# Top_Level.net
KiCad netlist of a schematic drawn in Altium Designer
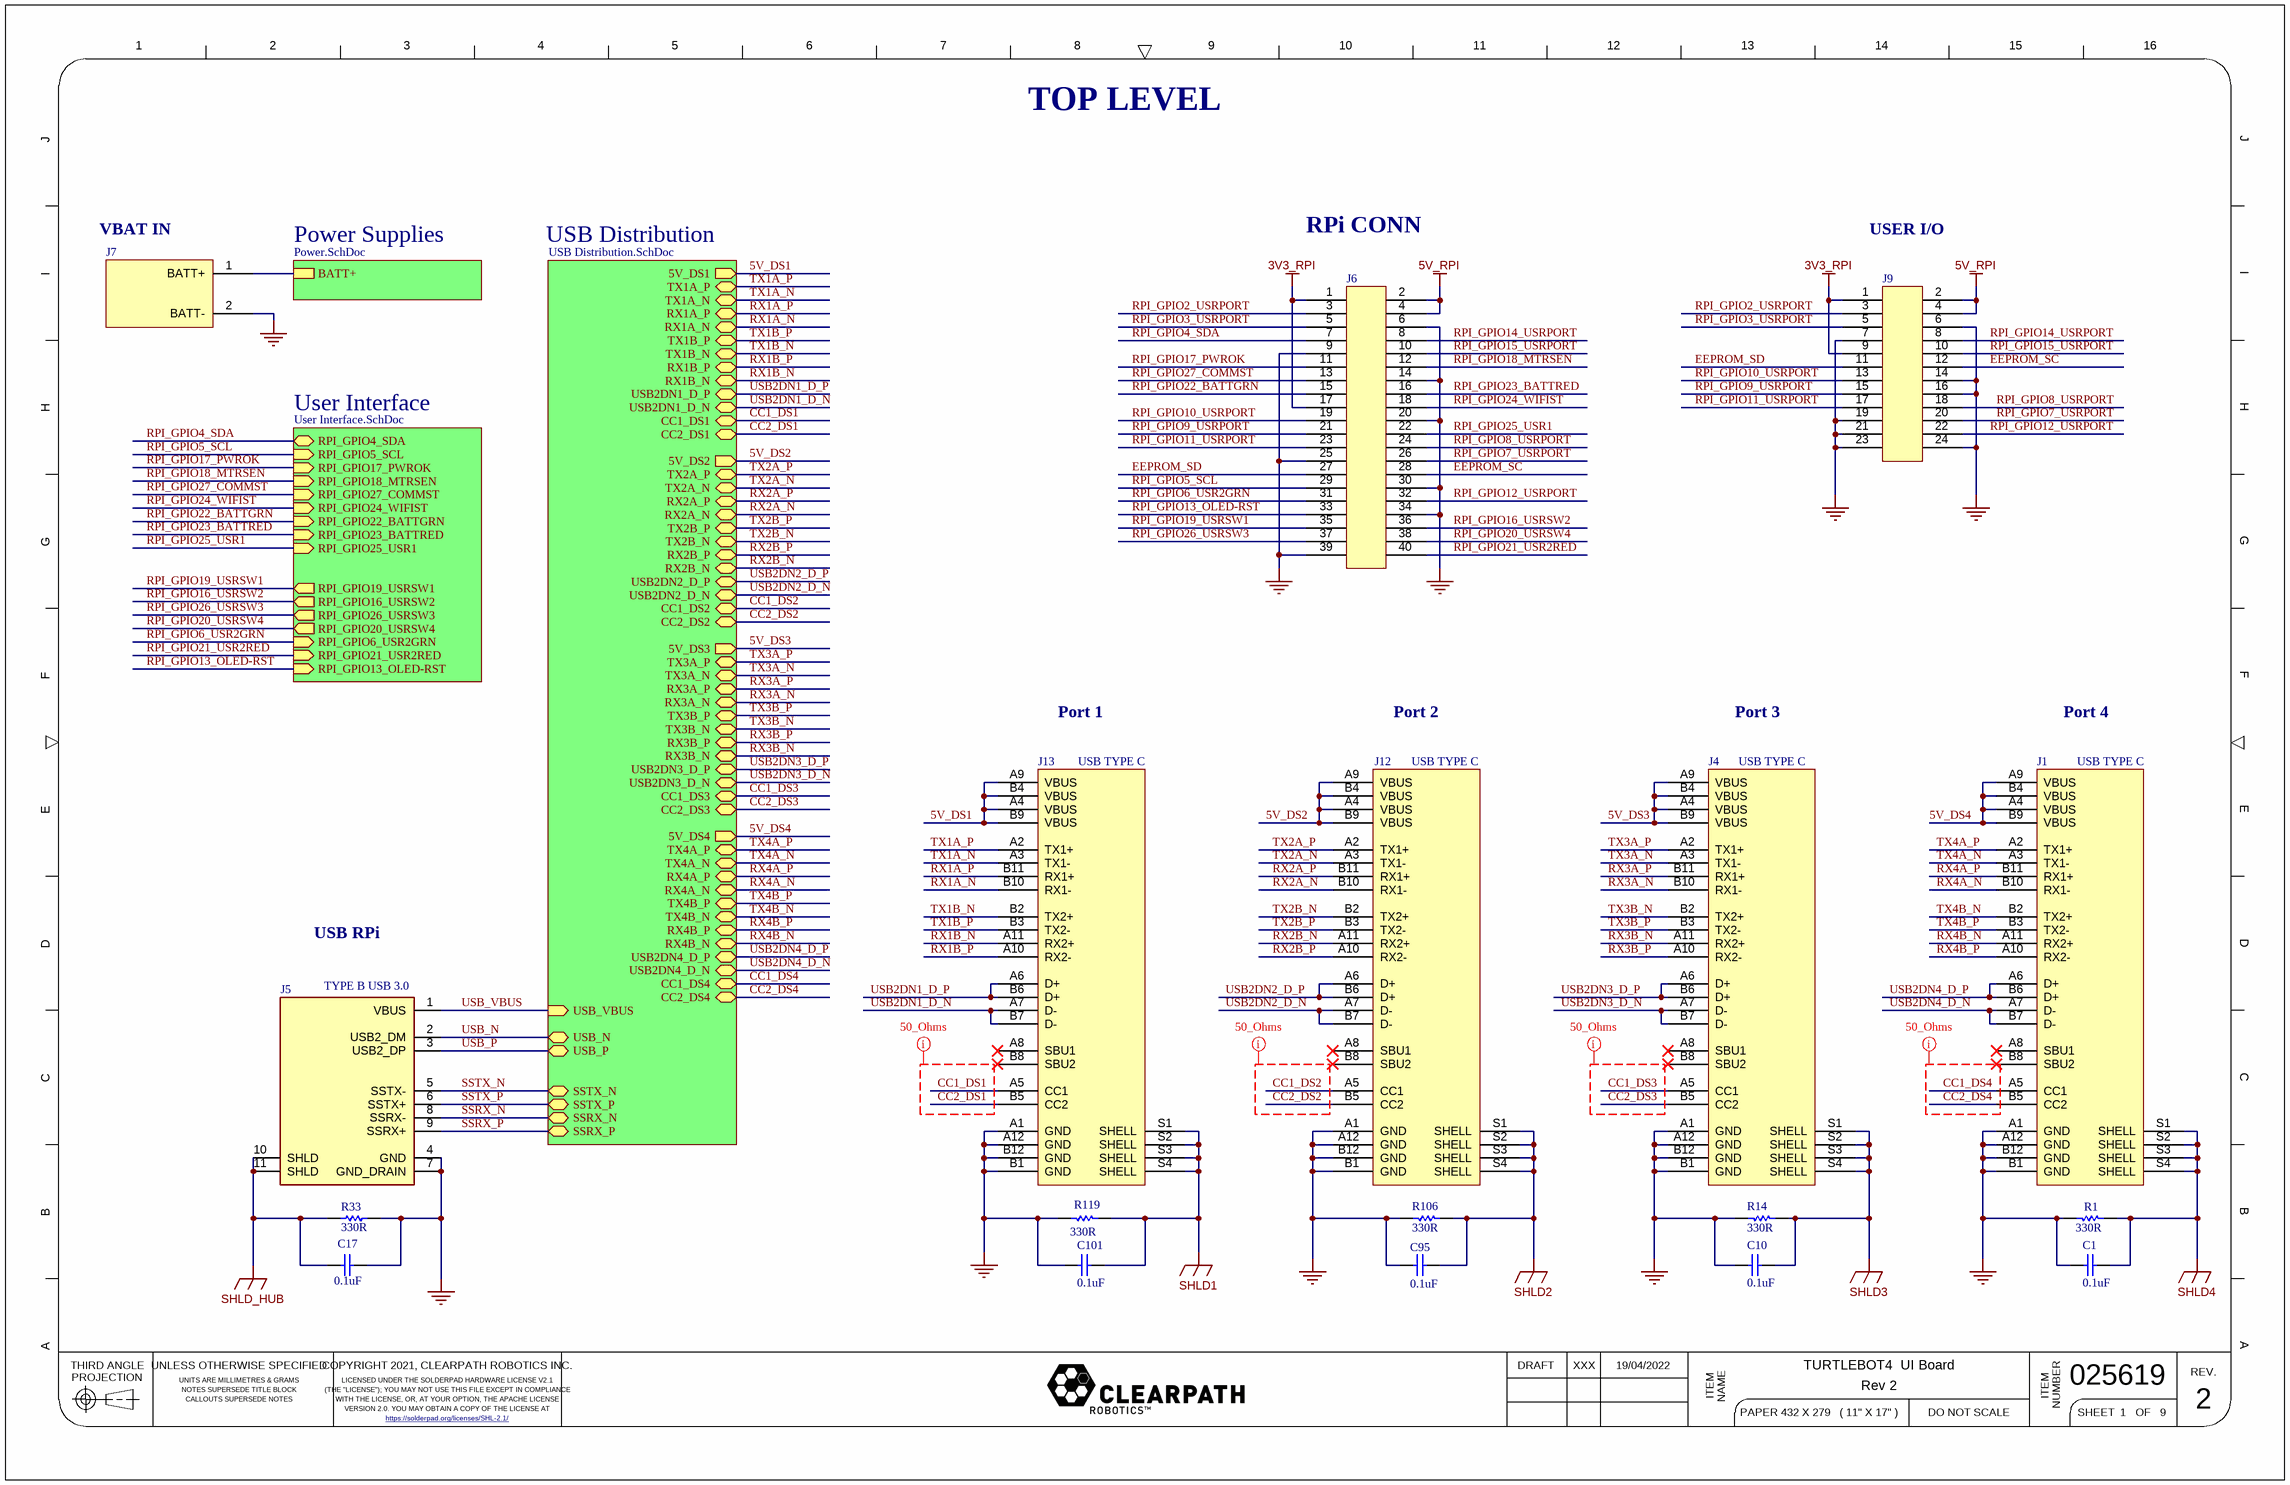
[diagram p0: Top Level.SchDoc]

(export (version "E")
  (design (tool "Eeschema 10.0.6"))
  (components
    (comp (ref "C1")
      (value "0.1uF")
      (footprint "C0805")
      (description "Capacitor")
      (fields (field (name "TOLERANCE") "10%") (field (name "VOLTAGE") "50V"))
      (libsource (lib "CPR_CommonDevices") (part "Capacitor _SMT"))
    )
    (comp (ref "C10")
      (value "0.1uF")
      (footprint "C0805")
      (description "Capacitor")
      (fields (field (name "TOLERANCE") "10%") (field (name "VOLTAGE") "50V"))
      (libsource (lib "CPR_CommonDevices") (part "Capacitor _SMT"))
    )
    (comp (ref "C17")
      (value "0.1uF")
      (footprint "C0805")
      (description "Capacitor")
      (fields (field (name "TOLERANCE") "10%") (field (name "VOLTAGE") "50V"))
      (libsource (lib "CPR_CommonDevices") (part "Capacitor _SMT"))
    )
    (comp (ref "C95")
      (value "0.1uF")
      (footprint "C0805")
      (description "Capacitor")
      (fields (field (name "TOLERANCE") "10%") (field (name "VOLTAGE") "50V"))
      (libsource (lib "CPR_CommonDevices") (part "Capacitor _SMT"))
    )
    (comp (ref "C101")
      (value "0.1uF")
      (footprint "C0805")
      (description "Capacitor")
      (fields (field (name "TOLERANCE") "10%") (field (name "VOLTAGE") "50V"))
      (libsource (lib "CPR_CommonDevices") (part "Capacitor _SMT"))
    )
    (comp (ref "J1")
      (value "USB TYPE C")
      (footprint "MOLEX_2012670005")
      (description "USB Type C receptacle")
      (fields (field (name "MFG") "Molex"))
      (libsource (lib "Molex 2012670005 USB Type C") (part "Molex_2012670005"))
    )
    (comp (ref "J4")
      (value "USB TYPE C")
      (footprint "MOLEX_2012670005")
      (description "USB Type C receptacle")
      (fields (field (name "MFG") "Molex"))
      (libsource (lib "Molex 2012670005 USB Type C") (part "Molex_2012670005"))
    )
    (comp (ref "J5")
      (value "TYPE B USB 3.0")
      (footprint "1003-024-02000")
      (description "CNC RA USB3.0 Type B")
      (fields (field (name "MFG") "CNC Tech"))
      (libsource (lib "CNC Tech 1003-024-02000 Conn") (part "CNC_1003-024-02000"))
    )
    (comp (ref "J6")
      (value "Conn_2X20_2")
      (footprint "Conn_2X20_SMT:Conn_2X20_SMT")
      (description "sourface mount. 2X20 pin connector meant to connect to ribbon cable")
      (libsource (lib "Conn_2X20_2") (part "Conn_2X20_2"))
    )
    (comp (ref "J7")
      (value "JST Power Connector")
      (footprint "General PCB Library:JST_S2B")
      (description "JST S2B-XH-A(LF)(SN)")
      (fields (field (name "MANUFACTURER") "JST"))
      (libsource (lib "JST_S2B-XH") (part "JST_S2B-XH-A(LF)(SN)"))
    )
    (comp (ref "J9")
      (value "AUX_CONNECTOR")
      (footprint "2X12_SMT:SULLINS_SBH11-NBPC-D12-SM-BK")
      (libsource (lib "Conn_2X12_SMT") (part "Conn_2X12_THU"))
    )
    (comp (ref "J12")
      (value "USB TYPE C")
      (footprint "MOLEX_2012670005")
      (description "USB Type C receptacle")
      (fields (field (name "MFG") "Molex"))
      (libsource (lib "Molex 2012670005 USB Type C") (part "Molex_2012670005"))
    )
    (comp (ref "J13")
      (value "USB TYPE C")
      (footprint "MOLEX_2012670005")
      (description "USB Type C receptacle")
      (fields (field (name "MFG") "Molex"))
      (libsource (lib "Molex 2012670005 USB Type C") (part "Molex_2012670005"))
    )
    (comp (ref "R1")
      (value "330R")
      (footprint "R0805")
      (description "Resistor")
      (fields (field (name "TOLERANCE") "5%") (field (name "MFG") "Yageo"))
      (libsource (lib "CPR_CommonDevices") (part "Resistor_SMT"))
    )
    (comp (ref "R14")
      (value "330R")
      (footprint "R0805")
      (description "Resistor")
      (fields (field (name "TOLERANCE") "5%") (field (name "MFG") "Yageo"))
      (libsource (lib "CPR_CommonDevices") (part "Resistor_SMT"))
    )
    (comp (ref "R33")
      (value "330R")
      (footprint "R0805")
      (description "Resistor")
      (fields (field (name "TOLERANCE") "5%") (field (name "MFG") "Yageo"))
      (libsource (lib "CPR_CommonDevices") (part "Resistor_SMT"))
    )
    (comp (ref "R106")
      (value "330R")
      (footprint "R0805")
      (description "Resistor")
      (fields (field (name "TOLERANCE") "5%") (field (name "MFG") "Yageo"))
      (libsource (lib "CPR_CommonDevices") (part "Resistor_SMT"))
    )
    (comp (ref "R119")
      (value "330R")
      (footprint "R0805")
      (description "Resistor")
      (fields (field (name "TOLERANCE") "5%") (field (name "MFG") "Yageo"))
      (libsource (lib "CPR_CommonDevices") (part "Resistor_SMT"))
    )
  )
  (nets
    (net (code "1") (name "/5V_DS1") (class "Default")
      (node (ref "J13") (pin "A4") (pinfunction "VBUS_A4") (pintype "passive"))
      (node (ref "J13") (pin "A9") (pinfunction "VBUS_A9") (pintype "passive"))
      (node (ref "J13") (pin "B4") (pinfunction "VBUS_B4") (pintype "passive"))
      (node (ref "J13") (pin "B9") (pinfunction "VBUS_B9") (pintype "passive"))
    )
    (net (code "2") (name "/5V_DS2") (class "Default")
      (node (ref "J12") (pin "A4") (pinfunction "VBUS_A4") (pintype "passive"))
      (node (ref "J12") (pin "A9") (pinfunction "VBUS_A9") (pintype "passive"))
      (node (ref "J12") (pin "B4") (pinfunction "VBUS_B4") (pintype "passive"))
      (node (ref "J12") (pin "B9") (pinfunction "VBUS_B9") (pintype "passive"))
    )
    (net (code "3") (name "/5V_DS3") (class "Default")
      (node (ref "J4") (pin "A4") (pinfunction "VBUS_A4") (pintype "passive"))
      (node (ref "J4") (pin "A9") (pinfunction "VBUS_A9") (pintype "passive"))
      (node (ref "J4") (pin "B4") (pinfunction "VBUS_B4") (pintype "passive"))
      (node (ref "J4") (pin "B9") (pinfunction "VBUS_B9") (pintype "passive"))
    )
    (net (code "4") (name "/5V_DS4") (class "Default")
      (node (ref "J1") (pin "A4") (pinfunction "VBUS_A4") (pintype "passive"))
      (node (ref "J1") (pin "A9") (pinfunction "VBUS_A9") (pintype "passive"))
      (node (ref "J1") (pin "B4") (pinfunction "VBUS_B4") (pintype "passive"))
      (node (ref "J1") (pin "B9") (pinfunction "VBUS_B9") (pintype "passive"))
    )
    (net (code "5") (name "/BATT+") (class "Default")
      (node (ref "J7") (pin "1") (pinfunction "BATT+_1") (pintype "passive"))
    )
    (net (code "6") (name "/CC1_DS1") (class "Default")
      (node (ref "J13") (pin "A5") (pinfunction "CC1_A5") (pintype "passive"))
    )
    (net (code "7") (name "/CC1_DS2") (class "Default")
      (node (ref "J12") (pin "A5") (pinfunction "CC1_A5") (pintype "passive"))
    )
    (net (code "8") (name "/CC1_DS3") (class "Default")
      (node (ref "J4") (pin "A5") (pinfunction "CC1_A5") (pintype "passive"))
    )
    (net (code "9") (name "/CC1_DS4") (class "Default")
      (node (ref "J1") (pin "A5") (pinfunction "CC1_A5") (pintype "passive"))
    )
    (net (code "10") (name "/CC2_DS1") (class "Default")
      (node (ref "J13") (pin "B5") (pinfunction "CC2_B5") (pintype "passive"))
    )
    (net (code "11") (name "/CC2_DS2") (class "Default")
      (node (ref "J12") (pin "B5") (pinfunction "CC2_B5") (pintype "passive"))
    )
    (net (code "12") (name "/CC2_DS3") (class "Default")
      (node (ref "J4") (pin "B5") (pinfunction "CC2_B5") (pintype "passive"))
    )
    (net (code "13") (name "/CC2_DS4") (class "Default")
      (node (ref "J1") (pin "B5") (pinfunction "CC2_B5") (pintype "passive"))
    )
    (net (code "14") (name "/EEPROM_SC") (class "Default")
      (node (ref "J6") (pin "28") (pintype "passive"))
      (node (ref "J9") (pin "12") (pintype "passive"))
    )
    (net (code "15") (name "/EEPROM_SD") (class "Default")
      (node (ref "J6") (pin "27") (pintype "passive"))
      (node (ref "J9") (pin "11") (pintype "passive"))
    )
    (net (code "16") (name "/RPI_GPIO2_USRPORT") (class "Default")
      (node (ref "J6") (pin "3") (pintype "passive"))
      (node (ref "J9") (pin "3") (pintype "passive"))
    )
    (net (code "17") (name "/RPI_GPIO3_USRPORT") (class "Default")
      (node (ref "J6") (pin "5") (pintype "passive"))
      (node (ref "J9") (pin "5") (pintype "passive"))
    )
    (net (code "18") (name "/RPI_GPIO4_SDA") (class "Default")
      (node (ref "J6") (pin "7") (pintype "passive"))
    )
    (net (code "19") (name "/RPI_GPIO5_SCL") (class "Default")
      (node (ref "J6") (pin "29") (pintype "passive"))
    )
    (net (code "20") (name "/RPI_GPIO6_USR2GRN") (class "Default")
      (node (ref "J6") (pin "31") (pintype "passive"))
    )
    (net (code "21") (name "/RPI_GPIO7_USRPORT") (class "Default")
      (node (ref "J6") (pin "26") (pintype "passive"))
      (node (ref "J9") (pin "20") (pintype "passive"))
    )
    (net (code "22") (name "/RPI_GPIO8_USRPORT") (class "Default")
      (node (ref "J6") (pin "24") (pintype "passive"))
      (node (ref "J9") (pin "18") (pintype "passive"))
    )
    (net (code "23") (name "/RPI_GPIO9_USRPORT") (class "Default")
      (node (ref "J6") (pin "21") (pintype "passive"))
      (node (ref "J9") (pin "15") (pintype "passive"))
    )
    (net (code "24") (name "/RPI_GPIO10_USRPORT") (class "Default")
      (node (ref "J6") (pin "19") (pintype "passive"))
      (node (ref "J9") (pin "13") (pintype "passive"))
    )
    (net (code "25") (name "/RPI_GPIO11_USRPORT") (class "Default")
      (node (ref "J6") (pin "23") (pintype "passive"))
      (node (ref "J9") (pin "17") (pintype "passive"))
    )
    (net (code "26") (name "/RPI_GPIO12_USRPORT") (class "Default")
      (node (ref "J6") (pin "32") (pintype "passive"))
      (node (ref "J9") (pin "22") (pintype "passive"))
    )
    (net (code "27") (name "/RPI_GPIO13_OLED-RST") (class "Default")
      (node (ref "J6") (pin "33") (pintype "passive"))
    )
    (net (code "28") (name "/RPI_GPIO14_USRPORT") (class "Default")
      (node (ref "J6") (pin "8") (pintype "passive"))
      (node (ref "J9") (pin "8") (pintype "passive"))
    )
    (net (code "29") (name "/RPI_GPIO15_USRPORT") (class "Default")
      (node (ref "J6") (pin "10") (pintype "passive"))
      (node (ref "J9") (pin "10") (pintype "passive"))
    )
    (net (code "30") (name "/RPI_GPIO16_USRSW2") (class "Default")
      (node (ref "J6") (pin "36") (pintype "passive"))
    )
    (net (code "31") (name "/RPI_GPIO17_PWROK") (class "Default")
      (node (ref "J6") (pin "11") (pintype "passive"))
    )
    (net (code "32") (name "/RPI_GPIO18_MTRSEN") (class "Default")
      (node (ref "J6") (pin "12") (pintype "passive"))
    )
    (net (code "33") (name "/RPI_GPIO19_USRSW1") (class "Default")
      (node (ref "J6") (pin "35") (pintype "passive"))
    )
    (net (code "34") (name "/RPI_GPIO20_USRSW4") (class "Default")
      (node (ref "J6") (pin "38") (pintype "passive"))
    )
    (net (code "35") (name "/RPI_GPIO21_USR2RED") (class "Default")
      (node (ref "J6") (pin "40") (pintype "passive"))
    )
    (net (code "36") (name "/RPI_GPIO22_BATTGRN") (class "Default")
      (node (ref "J6") (pin "15") (pintype "passive"))
    )
    (net (code "37") (name "/RPI_GPIO23_BATTRED") (class "Default")
      (node (ref "J6") (pin "16") (pintype "passive"))
    )
    (net (code "38") (name "/RPI_GPIO24_WIFIST") (class "Default")
      (node (ref "J6") (pin "18") (pintype "passive"))
    )
    (net (code "39") (name "/RPI_GPIO25_USR1") (class "Default")
      (node (ref "J6") (pin "22") (pintype "passive"))
    )
    (net (code "40") (name "/RPI_GPIO26_USRSW3") (class "Default")
      (node (ref "J6") (pin "37") (pintype "passive"))
    )
    (net (code "41") (name "/RPI_GPIO27_COMMST") (class "Default")
      (node (ref "J6") (pin "13") (pintype "passive"))
    )
    (net (code "42") (name "/RX1A_N") (class "Default")
      (node (ref "J13") (pin "B10") (pinfunction "RX1-_B10") (pintype "passive"))
    )
    (net (code "43") (name "/RX1A_P") (class "Default")
      (node (ref "J13") (pin "B11") (pinfunction "RX1+_B11") (pintype "passive"))
    )
    (net (code "44") (name "/RX1B_N") (class "Default")
      (node (ref "J13") (pin "A11") (pinfunction "RX2+_A11") (pintype "passive"))
    )
    (net (code "45") (name "/RX1B_P") (class "Default")
      (node (ref "J13") (pin "A10") (pinfunction "RX2-_A10") (pintype "passive"))
    )
    (net (code "46") (name "/RX2A_N") (class "Default")
      (node (ref "J12") (pin "B10") (pinfunction "RX1-_B10") (pintype "passive"))
    )
    (net (code "47") (name "/RX2A_P") (class "Default")
      (node (ref "J12") (pin "B11") (pinfunction "RX1+_B11") (pintype "passive"))
    )
    (net (code "48") (name "/RX2B_N") (class "Default")
      (node (ref "J12") (pin "A11") (pinfunction "RX2+_A11") (pintype "passive"))
    )
    (net (code "49") (name "/RX2B_P") (class "Default")
      (node (ref "J12") (pin "A10") (pinfunction "RX2-_A10") (pintype "passive"))
    )
    (net (code "50") (name "/RX3A_N") (class "Default")
      (node (ref "J4") (pin "B10") (pinfunction "RX1-_B10") (pintype "passive"))
    )
    (net (code "51") (name "/RX3A_P") (class "Default")
      (node (ref "J4") (pin "B11") (pinfunction "RX1+_B11") (pintype "passive"))
    )
    (net (code "52") (name "/RX3B_N") (class "Default")
      (node (ref "J4") (pin "A11") (pinfunction "RX2+_A11") (pintype "passive"))
    )
    (net (code "53") (name "/RX3B_P") (class "Default")
      (node (ref "J4") (pin "A10") (pinfunction "RX2-_A10") (pintype "passive"))
    )
    (net (code "54") (name "/RX4A_N") (class "Default")
      (node (ref "J1") (pin "B10") (pinfunction "RX1-_B10") (pintype "passive"))
    )
    (net (code "55") (name "/RX4A_P") (class "Default")
      (node (ref "J1") (pin "B11") (pinfunction "RX1+_B11") (pintype "passive"))
    )
    (net (code "56") (name "/RX4B_N") (class "Default")
      (node (ref "J1") (pin "A11") (pinfunction "RX2+_A11") (pintype "passive"))
    )
    (net (code "57") (name "/RX4B_P") (class "Default")
      (node (ref "J1") (pin "A10") (pinfunction "RX2-_A10") (pintype "passive"))
    )
    (net (code "58") (name "/SSRX_N") (class "Default")
      (node (ref "J5") (pin "8") (pinfunction "SSRX-_8") (pintype "passive"))
    )
    (net (code "59") (name "/SSRX_P") (class "Default")
      (node (ref "J5") (pin "9") (pinfunction "SSRX+_9") (pintype "passive"))
    )
    (net (code "60") (name "/SSTX_N") (class "Default")
      (node (ref "J5") (pin "5") (pinfunction "SSTX-_5") (pintype "passive"))
    )
    (net (code "61") (name "/SSTX_P") (class "Default")
      (node (ref "J5") (pin "6") (pinfunction "SSTX+_6") (pintype "passive"))
    )
    (net (code "62") (name "/TX1A_N") (class "Default")
      (node (ref "J13") (pin "A3") (pinfunction "TX1-_A3") (pintype "passive"))
    )
    (net (code "63") (name "/TX1A_P") (class "Default")
      (node (ref "J13") (pin "A2") (pinfunction "TX1+_A2") (pintype "passive"))
    )
    (net (code "64") (name "/TX1B_N") (class "Default")
      (node (ref "J13") (pin "B2") (pinfunction "TX2+_B2") (pintype "passive"))
    )
    (net (code "65") (name "/TX1B_P") (class "Default")
      (node (ref "J13") (pin "B3") (pinfunction "TX2-_B3") (pintype "passive"))
    )
    (net (code "66") (name "/TX2A_N") (class "Default")
      (node (ref "J12") (pin "A3") (pinfunction "TX1-_A3") (pintype "passive"))
    )
    (net (code "67") (name "/TX2A_P") (class "Default")
      (node (ref "J12") (pin "A2") (pinfunction "TX1+_A2") (pintype "passive"))
    )
    (net (code "68") (name "/TX2B_N") (class "Default")
      (node (ref "J12") (pin "B2") (pinfunction "TX2+_B2") (pintype "passive"))
    )
    (net (code "69") (name "/TX2B_P") (class "Default")
      (node (ref "J12") (pin "B3") (pinfunction "TX2-_B3") (pintype "passive"))
    )
    (net (code "70") (name "/TX3A_N") (class "Default")
      (node (ref "J4") (pin "A3") (pinfunction "TX1-_A3") (pintype "passive"))
    )
    (net (code "71") (name "/TX3A_P") (class "Default")
      (node (ref "J4") (pin "A2") (pinfunction "TX1+_A2") (pintype "passive"))
    )
    (net (code "72") (name "/TX3B_N") (class "Default")
      (node (ref "J4") (pin "B2") (pinfunction "TX2+_B2") (pintype "passive"))
    )
    (net (code "73") (name "/TX3B_P") (class "Default")
      (node (ref "J4") (pin "B3") (pinfunction "TX2-_B3") (pintype "passive"))
    )
    (net (code "74") (name "/TX4A_N") (class "Default")
      (node (ref "J1") (pin "A3") (pinfunction "TX1-_A3") (pintype "passive"))
    )
    (net (code "75") (name "/TX4A_P") (class "Default")
      (node (ref "J1") (pin "A2") (pinfunction "TX1+_A2") (pintype "passive"))
    )
    (net (code "76") (name "/TX4B_N") (class "Default")
      (node (ref "J1") (pin "B2") (pinfunction "TX2+_B2") (pintype "passive"))
    )
    (net (code "77") (name "/TX4B_P") (class "Default")
      (node (ref "J1") (pin "B3") (pinfunction "TX2-_B3") (pintype "passive"))
    )
    (net (code "78") (name "/USB2DN1_D_N") (class "Default")
      (node (ref "J13") (pin "A7") (pinfunction "D-_A7") (pintype "passive"))
      (node (ref "J13") (pin "B7") (pinfunction "D-_B7") (pintype "passive"))
    )
    (net (code "79") (name "/USB2DN1_D_P") (class "Default")
      (node (ref "J13") (pin "A6") (pinfunction "D+_A6") (pintype "passive"))
      (node (ref "J13") (pin "B6") (pinfunction "D+_B6") (pintype "passive"))
    )
    (net (code "80") (name "/USB2DN2_D_N") (class "Default")
      (node (ref "J12") (pin "A7") (pinfunction "D-_A7") (pintype "passive"))
      (node (ref "J12") (pin "B7") (pinfunction "D-_B7") (pintype "passive"))
    )
    (net (code "81") (name "/USB2DN2_D_P") (class "Default")
      (node (ref "J12") (pin "A6") (pinfunction "D+_A6") (pintype "passive"))
      (node (ref "J12") (pin "B6") (pinfunction "D+_B6") (pintype "passive"))
    )
    (net (code "82") (name "/USB2DN3_D_N") (class "Default")
      (node (ref "J4") (pin "A7") (pinfunction "D-_A7") (pintype "passive"))
      (node (ref "J4") (pin "B7") (pinfunction "D-_B7") (pintype "passive"))
    )
    (net (code "83") (name "/USB2DN3_D_P") (class "Default")
      (node (ref "J4") (pin "A6") (pinfunction "D+_A6") (pintype "passive"))
      (node (ref "J4") (pin "B6") (pinfunction "D+_B6") (pintype "passive"))
    )
    (net (code "84") (name "/USB2DN4_D_N") (class "Default")
      (node (ref "J1") (pin "A7") (pinfunction "D-_A7") (pintype "passive"))
      (node (ref "J1") (pin "B7") (pinfunction "D-_B7") (pintype "passive"))
    )
    (net (code "85") (name "/USB2DN4_D_P") (class "Default")
      (node (ref "J1") (pin "A6") (pinfunction "D+_A6") (pintype "passive"))
      (node (ref "J1") (pin "B6") (pinfunction "D+_B6") (pintype "passive"))
    )
    (net (code "86") (name "/USB_N") (class "Default")
      (node (ref "J5") (pin "2") (pinfunction "USB2_DM_2") (pintype "passive"))
    )
    (net (code "87") (name "/USB_P") (class "Default")
      (node (ref "J5") (pin "3") (pinfunction "USB2_DP_3") (pintype "passive"))
    )
    (net (code "88") (name "/USB_VBUS") (class "Default")
      (node (ref "J5") (pin "1") (pinfunction "VBUS_1") (pintype "passive"))
    )
    (net (code "89") (name "3V3_RPI") (class "Default")
      (node (ref "J6") (pin "1") (pintype "passive"))
      (node (ref "J6") (pin "17") (pintype "passive"))
      (node (ref "J9") (pin "1") (pintype "passive"))
      (node (ref "J9") (pin "9") (pintype "passive"))
    )
    (net (code "90") (name "5V_RPI") (class "Default")
      (node (ref "J6") (pin "2") (pintype "passive"))
      (node (ref "J6") (pin "4") (pintype "passive"))
      (node (ref "J9") (pin "2") (pintype "passive"))
      (node (ref "J9") (pin "4") (pintype "passive"))
    )
    (net (code "91") (name "GND") (class "Default")
      (node (ref "C1") (pin "2") (pinfunction "2_2") (pintype "passive"))
      (node (ref "C10") (pin "2") (pinfunction "2_2") (pintype "passive"))
      (node (ref "C101") (pin "2") (pinfunction "2_2") (pintype "passive"))
      (node (ref "C17") (pin "2") (pinfunction "2_2") (pintype "passive"))
      (node (ref "C95") (pin "2") (pinfunction "2_2") (pintype "passive"))
      (node (ref "J1") (pin "A1") (pinfunction "GND_A1") (pintype "passive"))
      (node (ref "J1") (pin "A12") (pinfunction "GND_A12") (pintype "passive"))
      (node (ref "J1") (pin "B1") (pinfunction "GND_B1") (pintype "passive"))
      (node (ref "J1") (pin "B12") (pinfunction "GND_B12") (pintype "passive"))
      (node (ref "J12") (pin "A1") (pinfunction "GND_A1") (pintype "passive"))
      (node (ref "J12") (pin "A12") (pinfunction "GND_A12") (pintype "passive"))
      (node (ref "J12") (pin "B1") (pinfunction "GND_B1") (pintype "passive"))
      (node (ref "J12") (pin "B12") (pinfunction "GND_B12") (pintype "passive"))
      (node (ref "J13") (pin "A1") (pinfunction "GND_A1") (pintype "passive"))
      (node (ref "J13") (pin "A12") (pinfunction "GND_A12") (pintype "passive"))
      (node (ref "J13") (pin "B1") (pinfunction "GND_B1") (pintype "passive"))
      (node (ref "J13") (pin "B12") (pinfunction "GND_B12") (pintype "passive"))
      (node (ref "J4") (pin "A1") (pinfunction "GND_A1") (pintype "passive"))
      (node (ref "J4") (pin "A12") (pinfunction "GND_A12") (pintype "passive"))
      (node (ref "J4") (pin "B1") (pinfunction "GND_B1") (pintype "passive"))
      (node (ref "J4") (pin "B12") (pinfunction "GND_B12") (pintype "passive"))
      (node (ref "J5") (pin "4") (pinfunction "GND_4") (pintype "passive"))
      (node (ref "J5") (pin "7") (pinfunction "GND_DRAIN_7") (pintype "passive"))
      (node (ref "J6") (pin "14") (pintype "passive"))
      (node (ref "J6") (pin "20") (pintype "passive"))
      (node (ref "J6") (pin "25") (pintype "passive"))
      (node (ref "J6") (pin "30") (pintype "passive"))
      (node (ref "J6") (pin "34") (pintype "passive"))
      (node (ref "J6") (pin "39") (pintype "passive"))
      (node (ref "J6") (pin "6") (pintype "passive"))
      (node (ref "J6") (pin "9") (pintype "passive"))
      (node (ref "J7") (pin "2") (pinfunction "BATT-_2") (pintype "passive"))
      (node (ref "J9") (pin "14") (pintype "passive"))
      (node (ref "J9") (pin "16") (pintype "passive"))
      (node (ref "J9") (pin "19") (pintype "passive"))
      (node (ref "J9") (pin "21") (pintype "passive"))
      (node (ref "J9") (pin "23") (pintype "passive"))
      (node (ref "J9") (pin "24") (pintype "passive"))
      (node (ref "J9") (pin "6") (pintype "passive"))
      (node (ref "J9") (pin "7") (pintype "passive"))
      (node (ref "R1") (pin "2") (pinfunction "2_2") (pintype "passive"))
      (node (ref "R106") (pin "2") (pinfunction "2_2") (pintype "passive"))
      (node (ref "R119") (pin "2") (pinfunction "2_2") (pintype "passive"))
      (node (ref "R14") (pin "2") (pinfunction "2_2") (pintype "passive"))
      (node (ref "R33") (pin "2") (pinfunction "2_2") (pintype "passive"))
    )
    (net (code "92") (name "SHLD1") (class "Default")
      (node (ref "C101") (pin "1") (pinfunction "1_1") (pintype "passive"))
      (node (ref "J13") (pin "S1") (pinfunction "SHELL_S1") (pintype "passive"))
      (node (ref "J13") (pin "S2") (pinfunction "SHELL_S2") (pintype "passive"))
      (node (ref "J13") (pin "S3") (pinfunction "SHELL_S3") (pintype "passive"))
      (node (ref "J13") (pin "S4") (pinfunction "SHELL_S4") (pintype "passive"))
      (node (ref "R119") (pin "1") (pinfunction "1_1") (pintype "passive"))
    )
    (net (code "93") (name "SHLD2") (class "Default")
      (node (ref "C95") (pin "1") (pinfunction "1_1") (pintype "passive"))
      (node (ref "J12") (pin "S1") (pinfunction "SHELL_S1") (pintype "passive"))
      (node (ref "J12") (pin "S2") (pinfunction "SHELL_S2") (pintype "passive"))
      (node (ref "J12") (pin "S3") (pinfunction "SHELL_S3") (pintype "passive"))
      (node (ref "J12") (pin "S4") (pinfunction "SHELL_S4") (pintype "passive"))
      (node (ref "R106") (pin "1") (pinfunction "1_1") (pintype "passive"))
    )
    (net (code "94") (name "SHLD3") (class "Default")
      (node (ref "C10") (pin "1") (pinfunction "1_1") (pintype "passive"))
      (node (ref "J4") (pin "S1") (pinfunction "SHELL_S1") (pintype "passive"))
      (node (ref "J4") (pin "S2") (pinfunction "SHELL_S2") (pintype "passive"))
      (node (ref "J4") (pin "S3") (pinfunction "SHELL_S3") (pintype "passive"))
      (node (ref "J4") (pin "S4") (pinfunction "SHELL_S4") (pintype "passive"))
      (node (ref "R14") (pin "1") (pinfunction "1_1") (pintype "passive"))
    )
    (net (code "95") (name "SHLD4") (class "Default")
      (node (ref "C1") (pin "1") (pinfunction "1_1") (pintype "passive"))
      (node (ref "J1") (pin "S1") (pinfunction "SHELL_S1") (pintype "passive"))
      (node (ref "J1") (pin "S2") (pinfunction "SHELL_S2") (pintype "passive"))
      (node (ref "J1") (pin "S3") (pinfunction "SHELL_S3") (pintype "passive"))
      (node (ref "J1") (pin "S4") (pinfunction "SHELL_S4") (pintype "passive"))
      (node (ref "R1") (pin "1") (pinfunction "1_1") (pintype "passive"))
    )
    (net (code "96") (name "SHLD_HUB") (class "Default")
      (node (ref "C17") (pin "1") (pinfunction "1_1") (pintype "passive"))
      (node (ref "J5") (pin "10") (pinfunction "SHLD_10") (pintype "passive"))
      (node (ref "J5") (pin "11") (pinfunction "SHLD_11") (pintype "passive"))
      (node (ref "R33") (pin "1") (pinfunction "1_1") (pintype "passive"))
    )
    (net (code "97") (name "unconnected-(J1-SBU1-PadA8)") (class "Default")
      (node (ref "J1") (pin "A8") (pinfunction "SBU1_A8") (pintype "passive+no_connect"))
    )
    (net (code "98") (name "unconnected-(J1-SBU2-PadB8)") (class "Default")
      (node (ref "J1") (pin "B8") (pinfunction "SBU2_B8") (pintype "passive+no_connect"))
    )
    (net (code "99") (name "unconnected-(J4-SBU1-PadA8)") (class "Default")
      (node (ref "J4") (pin "A8") (pinfunction "SBU1_A8") (pintype "passive+no_connect"))
    )
    (net (code "100") (name "unconnected-(J4-SBU2-PadB8)") (class "Default")
      (node (ref "J4") (pin "B8") (pinfunction "SBU2_B8") (pintype "passive+no_connect"))
    )
    (net (code "101") (name "unconnected-(J12-SBU1-PadA8)") (class "Default")
      (node (ref "J12") (pin "A8") (pinfunction "SBU1_A8") (pintype "passive+no_connect"))
    )
    (net (code "102") (name "unconnected-(J12-SBU2-PadB8)") (class "Default")
      (node (ref "J12") (pin "B8") (pinfunction "SBU2_B8") (pintype "passive+no_connect"))
    )
    (net (code "103") (name "unconnected-(J13-SBU1-PadA8)") (class "Default")
      (node (ref "J13") (pin "A8") (pinfunction "SBU1_A8") (pintype "passive+no_connect"))
    )
    (net (code "104") (name "unconnected-(J13-SBU2-PadB8)") (class "Default")
      (node (ref "J13") (pin "B8") (pinfunction "SBU2_B8") (pintype "passive+no_connect"))
    )
  )
)
